# LTC4150_BOB_V01.net
KiCad netlist of a schematic drawn in EAGLE
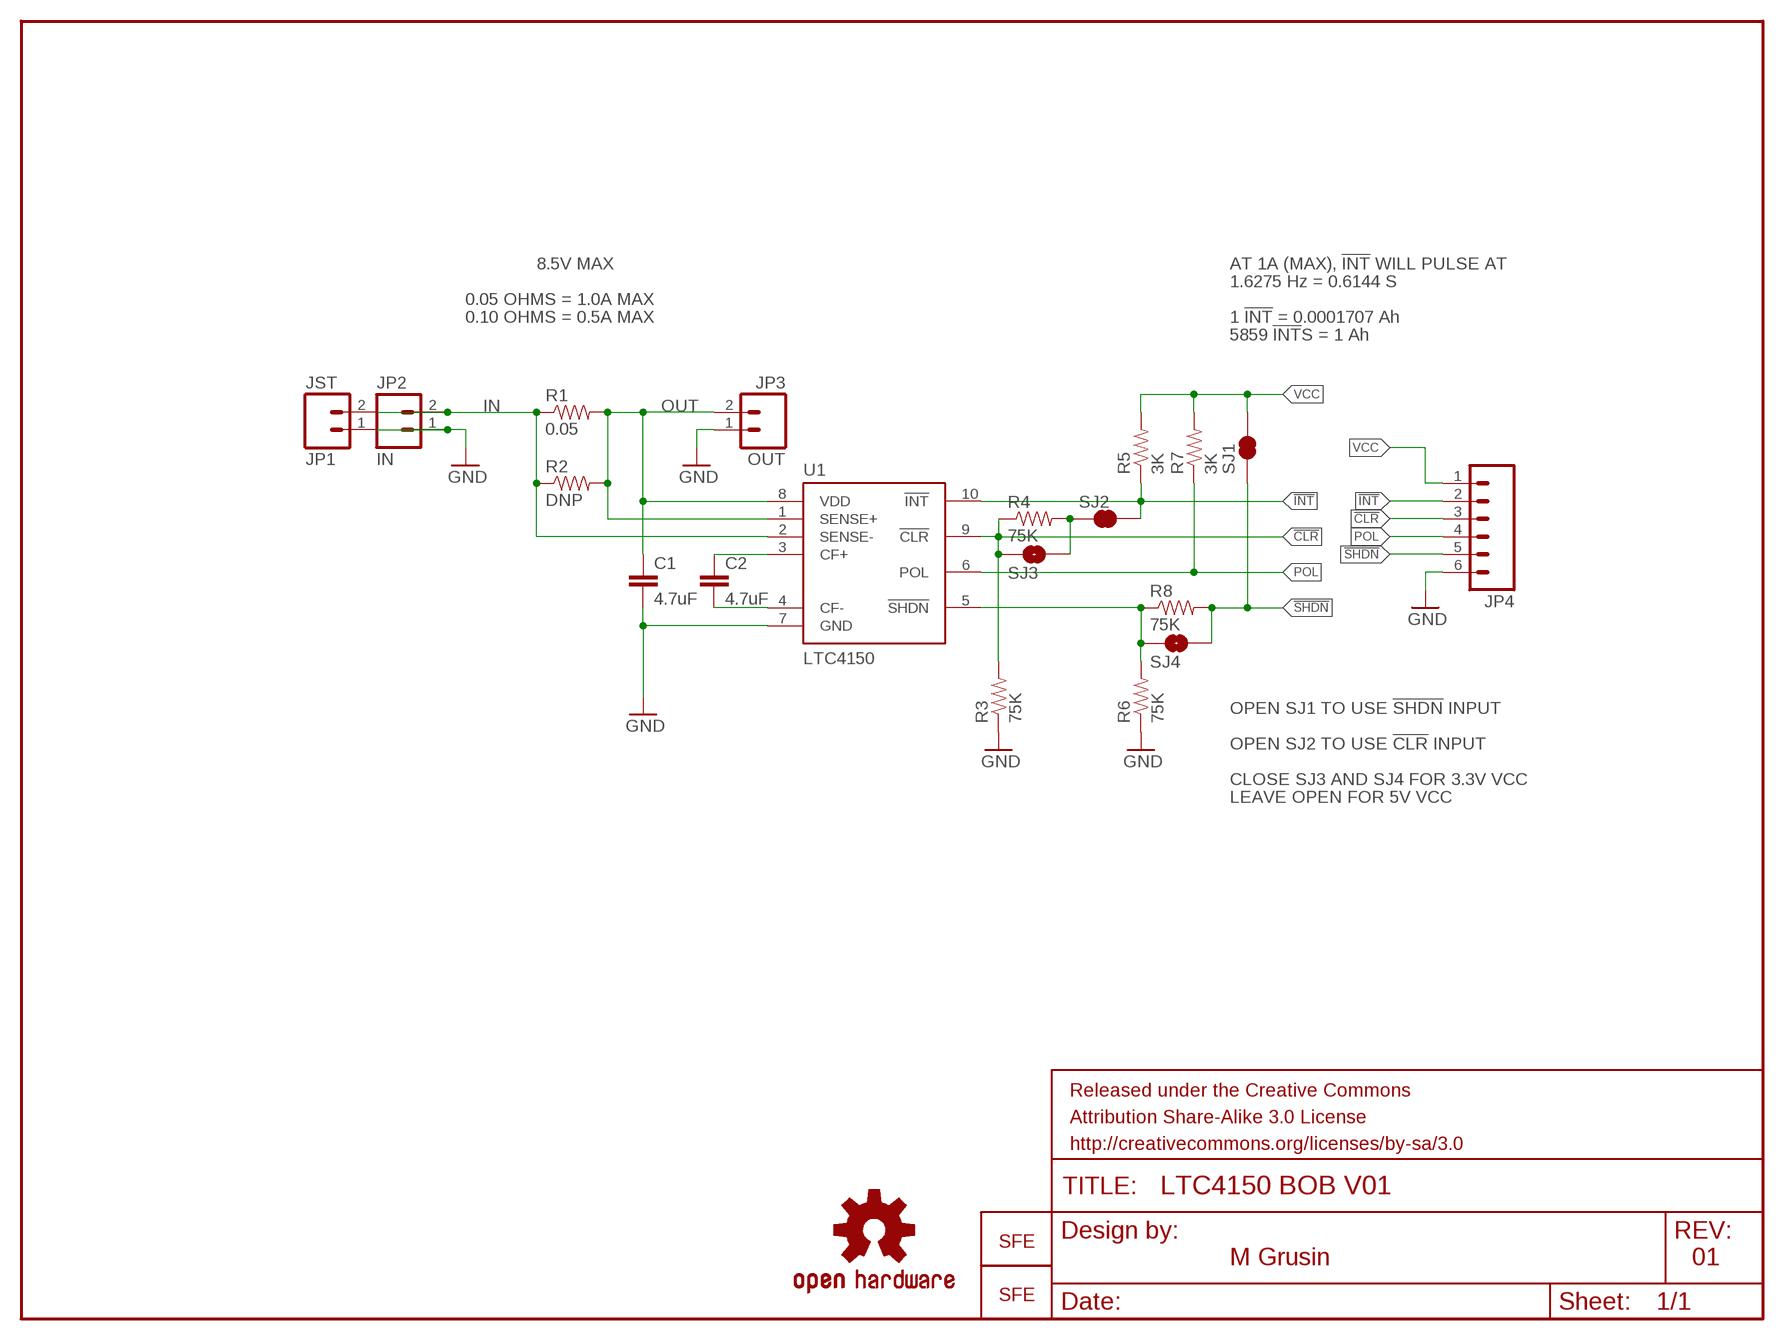
[diagram p0: schematic, sheet 1]

(export (version "E")
  (design (tool "Eeschema 10.0.6"))
  (components
    (comp (ref "C1")
      (value "4.7uF")
      (footprint "eagle-import:0603-CAP")
      (libsource (lib "eagle-import") (part "CAP0603-CAP"))
    )
    (comp (ref "C2")
      (value "4.7uF")
      (footprint "eagle-import:0603-CAP")
      (libsource (lib "eagle-import") (part "CAP0603-CAP"))
    )
    (comp (ref "FRAME1")
      (value "FRAME-LETTER")
      (footprint "eagle-import:CREATIVE_COMMONS")
      (libsource (lib "eagle-import") (part "FRAME-LETTER"))
    )
    (comp (ref "JP1")
      (value "JST")
      (footprint "eagle-import:JST-2-SMD")
      (libsource (lib "eagle-import") (part "M02-JST-2MM-SMT"))
    )
    (comp (ref "JP2")
      (value "IN")
      (footprint "eagle-import:1X02")
      (libsource (lib "eagle-import") (part "M02PTH"))
    )
    (comp (ref "JP3")
      (value "OUT")
      (footprint "eagle-import:1X02")
      (libsource (lib "eagle-import") (part "M02PTH"))
    )
    (comp (ref "JP4")
      (value "M06SIP")
      (footprint "eagle-import:1X06")
      (libsource (lib "eagle-import") (part "M06SIP"))
    )
    (comp (ref "LOGO1")
      (value "OSHW-LOGOS")
      (footprint "eagle-import:OSHW-LOGO-S")
      (libsource (lib "eagle-import") (part "OSHW-LOGOS"))
    )
    (comp (ref "LOGO2")
      (value "LOGO-SFENW2")
      (footprint "eagle-import:SFE-NEW-WEB")
      (libsource (lib "eagle-import") (part "LOGO-SFENW2"))
    )
    (comp (ref "LOGO3")
      (value "LOGO-SFESK")
      (footprint "eagle-import:SFE-LOGO-FLAME")
      (libsource (lib "eagle-import") (part "LOGO-SFESK"))
    )
    (comp (ref "R1")
      (value "0.05")
      (footprint "eagle-import:0805")
      (libsource (lib "eagle-import") (part "RESISTOR0805-RES"))
    )
    (comp (ref "R2")
      (value "DNP")
      (footprint "eagle-import:AXIAL-0.3")
      (libsource (lib "eagle-import") (part "RESISTORAXIAL-0.3"))
    )
    (comp (ref "R3")
      (value "75K")
      (footprint "eagle-import:0603-RES")
      (libsource (lib "eagle-import") (part "RESISTOR0603-RES"))
    )
    (comp (ref "R4")
      (value "75K")
      (footprint "eagle-import:0603-RES")
      (libsource (lib "eagle-import") (part "RESISTOR0603-RES"))
    )
    (comp (ref "R5")
      (value "3K")
      (footprint "eagle-import:0603-RES")
      (libsource (lib "eagle-import") (part "RESISTOR0603-RES"))
    )
    (comp (ref "R6")
      (value "75K")
      (footprint "eagle-import:0603-RES")
      (libsource (lib "eagle-import") (part "RESISTOR0603-RES"))
    )
    (comp (ref "R7")
      (value "3K")
      (footprint "eagle-import:0603-RES")
      (libsource (lib "eagle-import") (part "RESISTOR0603-RES"))
    )
    (comp (ref "R8")
      (value "75K")
      (footprint "eagle-import:0603-RES")
      (libsource (lib "eagle-import") (part "RESISTOR0603-RES"))
    )
    (comp (ref "SJ1")
      (value "SOLDERJUMPERNC")
      (footprint "eagle-import:SJ_2S")
      (libsource (lib "eagle-import") (part "mike-temp_SOLDERJUMPERNC"))
    )
    (comp (ref "SJ2")
      (value "SOLDERJUMPERNC")
      (footprint "eagle-import:SJ_2S")
      (libsource (lib "eagle-import") (part "SOLDERJUMPERNC"))
    )
    (comp (ref "SJ3")
      (value "SOLDERJUMPERNO")
      (footprint "eagle-import:SJ_2S-NO")
      (libsource (lib "eagle-import") (part "mike-temp_SOLDERJUMPERNO"))
    )
    (comp (ref "SJ4")
      (value "SOLDERJUMPERNO")
      (footprint "eagle-import:SJ_2S-NO")
      (libsource (lib "eagle-import") (part "mike-temp_SOLDERJUMPERNO"))
    )
    (comp (ref "U1")
      (value "LTC4150")
      (footprint "eagle-import:MSOP10")
      (libsource (lib "eagle-import") (part "LTC4150"))
    )
  )
  (nets
    (net (code "1") (name "/IN") (class "Default")
      (node (ref "JP1") (pin "2") (pinfunction "1_2") (pintype "passive"))
      (node (ref "JP2") (pin "2") (pinfunction "2_2") (pintype "passive"))
      (node (ref "R1") (pin "1") (pinfunction "1_1") (pintype "passive"))
      (node (ref "R2") (pin "P$1") (pinfunction "1_P$1") (pintype "passive"))
      (node (ref "U1") (pin "2") (pinfunction "SENSE-_2") (pintype "bidirectional"))
    )
    (net (code "2") (name "/OUT") (class "Default")
      (node (ref "C1") (pin "1") (pinfunction "1_1") (pintype "passive"))
      (node (ref "JP3") (pin "2") (pinfunction "2_2") (pintype "passive"))
      (node (ref "R1") (pin "2") (pinfunction "2_2") (pintype "passive"))
      (node (ref "R2") (pin "P$2") (pinfunction "2_P$2") (pintype "passive"))
      (node (ref "U1") (pin "1") (pinfunction "SENSE+_1") (pintype "bidirectional"))
      (node (ref "U1") (pin "8") (pinfunction "VDD_8") (pintype "power_in"))
    )
    (net (code "3") (name "/~{CLR}") (class "Default")
      (node (ref "JP4") (pin "3") (pinfunction "3_3") (pintype "passive"))
      (node (ref "R3") (pin "2") (pinfunction "2_2") (pintype "passive"))
      (node (ref "R4") (pin "1") (pinfunction "1_1") (pintype "passive"))
      (node (ref "SJ3") (pin "1") (pinfunction "1_1") (pintype "passive"))
      (node (ref "U1") (pin "9") (pinfunction "~{CLR}_9") (pintype "bidirectional"))
    )
    (net (code "4") (name "/~{INT}") (class "Default")
      (node (ref "JP4") (pin "2") (pinfunction "2_2") (pintype "passive"))
      (node (ref "R5") (pin "1") (pinfunction "1_1") (pintype "passive"))
      (node (ref "SJ2") (pin "2") (pinfunction "2_2") (pintype "passive"))
      (node (ref "U1") (pin "10") (pinfunction "~{INT}_10") (pintype "bidirectional"))
    )
    (net (code "5") (name "/~{SHDN}") (class "Default")
      (node (ref "JP4") (pin "5") (pinfunction "5_5") (pintype "passive"))
      (node (ref "R8") (pin "2") (pinfunction "2_2") (pintype "passive"))
      (node (ref "SJ1") (pin "2") (pinfunction "2_2") (pintype "passive"))
      (node (ref "SJ4") (pin "2") (pinfunction "2_2") (pintype "passive"))
    )
    (net (code "6") (name "GND") (class "Default")
      (node (ref "C1") (pin "2") (pinfunction "2_2") (pintype "passive"))
      (node (ref "JP1") (pin "1") (pinfunction "2_1") (pintype "passive"))
      (node (ref "JP2") (pin "1") (pinfunction "1_1") (pintype "passive"))
      (node (ref "JP3") (pin "1") (pinfunction "1_1") (pintype "passive"))
      (node (ref "JP4") (pin "6") (pinfunction "6_6") (pintype "passive"))
      (node (ref "R3") (pin "1") (pinfunction "1_1") (pintype "passive"))
      (node (ref "R6") (pin "1") (pinfunction "1_1") (pintype "passive"))
      (node (ref "U1") (pin "7") (pinfunction "GND_7") (pintype "power_in"))
    )
    (net (code "7") (name "Net-(R4-Pad2)") (class "Default")
      (node (ref "R4") (pin "2") (pinfunction "2_2") (pintype "passive"))
      (node (ref "SJ2") (pin "1") (pinfunction "1_1") (pintype "passive"))
      (node (ref "SJ3") (pin "2") (pinfunction "2_2") (pintype "passive"))
    )
    (net (code "8") (name "Net-(U1-CF+)") (class "Default")
      (node (ref "C2") (pin "1") (pinfunction "1_1") (pintype "passive"))
      (node (ref "U1") (pin "3") (pinfunction "CF+_3") (pintype "bidirectional"))
    )
    (net (code "9") (name "Net-(U1-CF-)") (class "Default")
      (node (ref "C2") (pin "2") (pinfunction "2_2") (pintype "passive"))
      (node (ref "U1") (pin "4") (pinfunction "CF-_4") (pintype "bidirectional"))
    )
    (net (code "10") (name "Net-(U1-~{SHDN})") (class "Default")
      (node (ref "R6") (pin "2") (pinfunction "2_2") (pintype "passive"))
      (node (ref "R8") (pin "1") (pinfunction "1_1") (pintype "passive"))
      (node (ref "SJ4") (pin "1") (pinfunction "1_1") (pintype "passive"))
      (node (ref "U1") (pin "5") (pinfunction "~{SHDN}_5") (pintype "input"))
    )
    (net (code "11") (name "POL") (class "Default")
      (node (ref "JP4") (pin "4") (pinfunction "4_4") (pintype "passive"))
      (node (ref "R7") (pin "1") (pinfunction "1_1") (pintype "passive"))
      (node (ref "U1") (pin "6") (pinfunction "POL_6") (pintype "bidirectional"))
    )
    (net (code "12") (name "VCC") (class "Default")
      (node (ref "JP4") (pin "1") (pinfunction "1_1") (pintype "passive"))
      (node (ref "R5") (pin "2") (pinfunction "2_2") (pintype "passive"))
      (node (ref "R7") (pin "2") (pinfunction "2_2") (pintype "passive"))
      (node (ref "SJ1") (pin "1") (pinfunction "1_1") (pintype "passive"))
    )
  )
)
